# MotoBot.net
KiCad netlist of a schematic drawn in Altium Designer
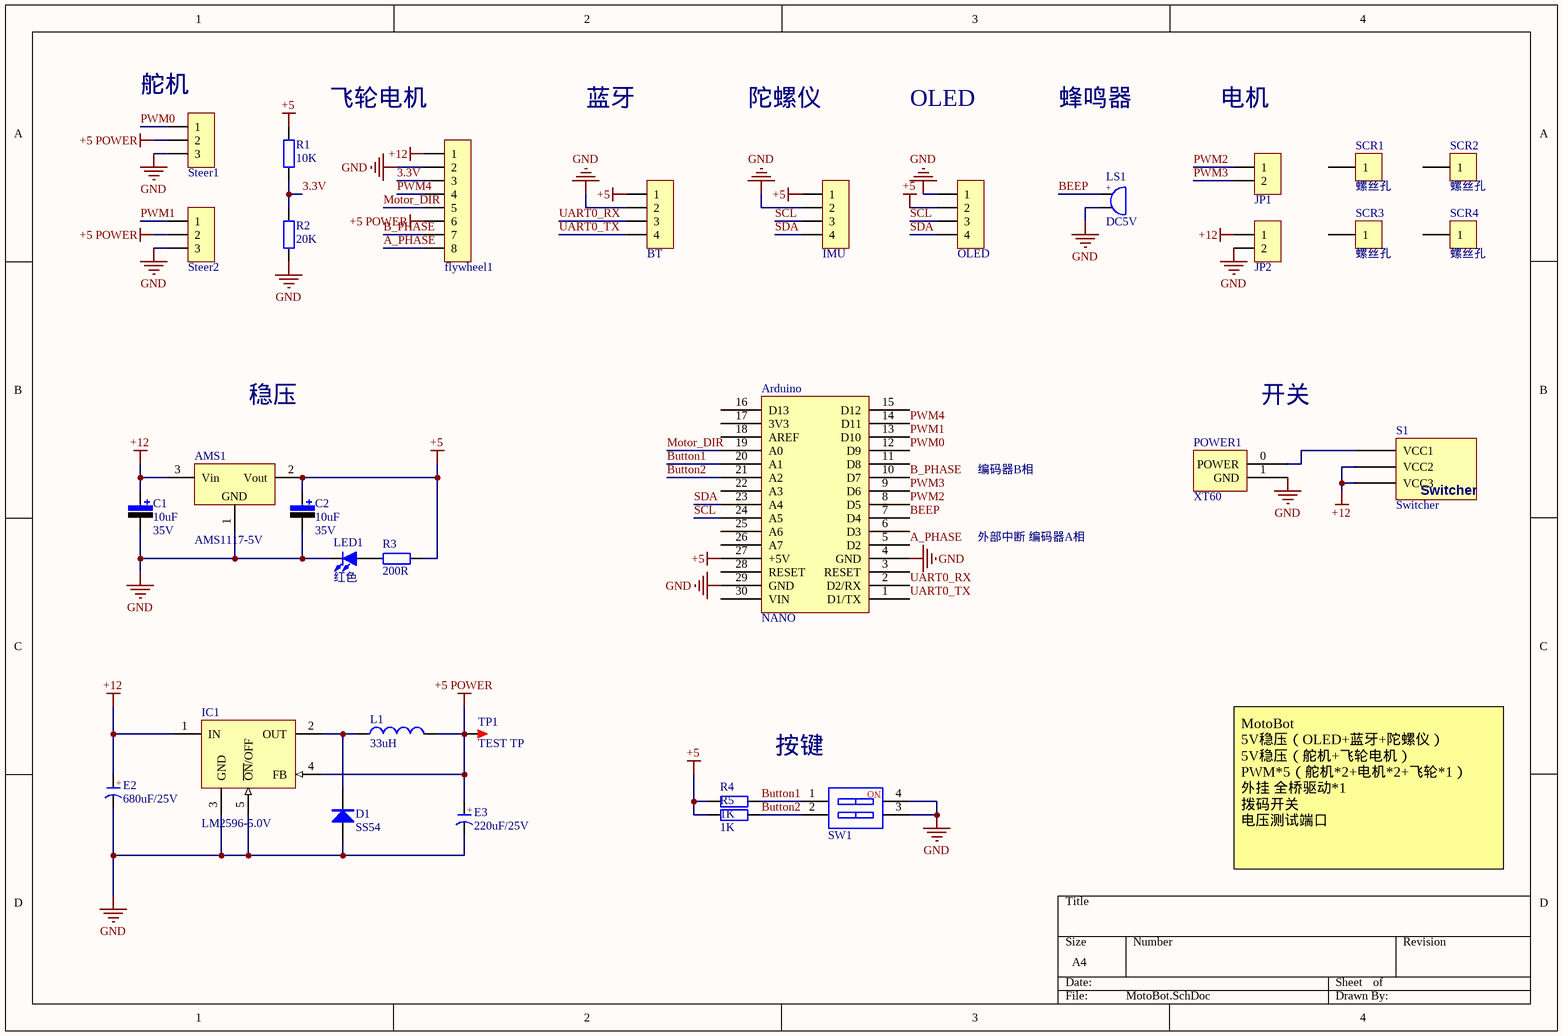
[diagram p0: MotoBot.SchDoc]

(export (version "E")
  (design (tool "Eeschema 10.0.6"))
  (components
    (comp (ref "AMS1")
      (value "AMS1117-5V")
      (footprint "SOT-223")
      (description "三端稳压芯片")
      (fields (field (name "版权归属") "黎明电子style"))
      (libsource (lib "IC芯片") (part "AMS1117"))
    )
    (comp (ref "Arduino") (value "NANO") (footprint "NANO") (libsource (lib "附加模块") (part "NANO")))
    (comp (ref "BT")
      (value "HDR-1X4")
      (footprint "HDR-1X4_M")
      (description "4P接插件")
      (fields (field (name "版权归属") "黎明电子style"))
      (libsource (lib "接插件") (part "Header 4"))
    )
    (comp (ref "C1")
      (value "10uF")
      (footprint "CAP-7343")
      (description "极性电解电容")
      (fields
        (field (name "VOL") "35V")
        (field (name "Comment") "Cap Pol")
        (field (name "PUBLISHER") "Altium Limited")
      )
      (libsource (lib "Fszhang") (part "Cap Pol"))
    )
    (comp (ref "C2")
      (value "10uF")
      (footprint "CAP-7343")
      (description "极性电解电容")
      (fields
        (field (name "VOL") "35V")
        (field (name "Comment") "Cap Pol")
        (field (name "PUBLISHER") "Altium Limited")
      )
      (libsource (lib "Fszhang") (part "Cap Pol"))
    )
    (comp (ref "D1")
      (value "SS54")
      (footprint "SMA")
      (description "肖特基二极管")
      (fields (field (name "版权归属") "源创客"))
      (libsource (lib "8.1   - 二极管-整流桥") (part "SS14"))
    )
    (comp (ref "E2")
      (value "680uF/25V")
      (footprint "CAP 3.5*8*11.5")
      (description "直插电解电容")
      (fields (field (name "版权归属") "源创客"))
      (libsource (lib "3.1   - 电阻-电容-电感") (part "C-CAP"))
    )
    (comp (ref "E3")
      (value "220uF/25V")
      (footprint "CAP 2.0*5*11")
      (description "直插电解电容")
      (fields (field (name "版权归属") "源创客"))
      (libsource (lib "3.1   - 电阻-电容-电感") (part "C-CAP"))
    )
    (comp (ref "flywheel1")
      (value "HDR-1X8")
      (footprint "ZH1.5-WI-8P")
      (description "8P接插件")
      (fields (field (name "版权归属") "源创客"))
      (libsource (lib "4.3   - 接插件-脚距1.5") (part "Header 8"))
    )
    (comp (ref "IC1")
      (value "LM2596-5.0V")
      (footprint "TO263-5A")
      (description "DC降压芯片")
      (fields (field (name "版权归属") "源创客"))
      (libsource (lib "1.3   - 电源类芯片") (part "LM2596-5.0"))
    )
    (comp (ref "IMU")
      (value "HDR-1X4")
      (footprint "HDR-1X4_M")
      (description "4P接插件")
      (fields (field (name "版权归属") "黎明电子style"))
      (libsource (lib "接插件") (part "Header 4"))
    )
    (comp (ref "JP1")
      (value "HDR-1X2")
      (footprint "KF128-5.08-2P")
      (description "2P接插件")
      (fields (field (name "版权归属") "源创客"))
      (libsource (lib "4.10 - 接插件-脚距5.08") (part "Header 2"))
    )
    (comp (ref "JP2")
      (value "HDR-1X2")
      (footprint "KF128-5.08-2P")
      (description "2P接插件")
      (fields (field (name "版权归属") "源创客"))
      (libsource (lib "4.10 - 接插件-脚距5.08") (part "Header 2"))
    )
    (comp (ref "L1") (value "33uH") (footprint "CDRH74") (libsource (lib "K60") (part "Inductor")))
    (comp (ref "LED1")
      (value "红色")
      (footprint "LED 0805W")
      (description "贴片LED")
      (fields (field (name "版权归属") "源创客"))
      (libsource (lib "9.1   - LED") (part "LED-SMD"))
    )
    (comp (ref "LS1")
      (value "DC5V")
      (footprint "BEEP 5x9x5.5")
      (description "蜂鸣器")
      (fields (field (name "版权归属") "源创客"))
      (libsource (lib "15.1 - 未分类器件") (part "BEEP"))
    )
    (comp (ref "OLED")
      (value "HDR-1X4")
      (footprint "HDR-1X4_M")
      (description "4P接插件")
      (fields (field (name "版权归属") "黎明电子style"))
      (libsource (lib "接插件") (part "Header 4"))
    )
    (comp (ref "POWER1")
      (value "XT60")
      (footprint "XT60")
      (libsource (lib "Integrated_Library_CAE") (part "XT60"))
    )
    (comp (ref "R1")
      (value "10K")
      (footprint "R 0805_L")
      (description "贴片电阻")
      (fields (field (name "版权归属") "源创客"))
      (libsource (lib "3.1   - 电阻-电容-电感") (part "R"))
    )
    (comp (ref "R2")
      (value "20K")
      (footprint "R 0805_L")
      (description "贴片电阻")
      (fields (field (name "版权归属") "源创客"))
      (libsource (lib "3.1   - 电阻-电容-电感") (part "R"))
    )
    (comp (ref "R3")
      (value "200R")
      (footprint "R 0805_L")
      (description "贴片电阻")
      (fields (field (name "版权归属") "源创客"))
      (libsource (lib "3.1   - 电阻-电容-电感") (part "R"))
    )
    (comp (ref "R4")
      (value "1K")
      (footprint "R 0805_L")
      (description "贴片电阻")
      (fields (field (name "版权归属") "源创客"))
      (libsource (lib "3.1   - 电阻-电容-电感") (part "R"))
    )
    (comp (ref "R5")
      (value "1K")
      (footprint "R 0805_L")
      (description "贴片电阻")
      (fields (field (name "版权归属") "源创客"))
      (libsource (lib "3.1   - 电阻-电容-电感") (part "R"))
    )
    (comp (ref "S1")
      (value "Switcher")
      (footprint "ThreeSwitcher")
      (libsource (lib "K60") (part "3_Switcher"))
    )
    (comp (ref "SCR1")
      (value "螺丝孔")
      (footprint "LQ_SCROW3&5mm")
      (description "Connector")
      (libsource (lib "LQ-RT1052VCMBVF") (part "CON1"))
    )
    (comp (ref "SCR2")
      (value "螺丝孔")
      (footprint "LQ_SCROW3&5mm")
      (description "Connector")
      (libsource (lib "LQ-RT1052VCMBVF") (part "CON1"))
    )
    (comp (ref "SCR3")
      (value "螺丝孔")
      (footprint "LQ_SCROW3&5mm")
      (description "Connector")
      (libsource (lib "LQ-RT1052VCMBVF") (part "CON1"))
    )
    (comp (ref "SCR4")
      (value "螺丝孔")
      (footprint "LQ_SCROW3&5mm")
      (description "Connector")
      (libsource (lib "LQ-RT1052VCMBVF") (part "CON1"))
    )
    (comp (ref "Steer1")
      (value "HDR-1X3")
      (footprint "HDR-1X3")
      (description "3P接插件")
      (fields (field (name "版权归属") "黎明电子style"))
      (libsource (lib "接插件") (part "Header 3"))
    )
    (comp (ref "Steer2")
      (value "HDR-1X3")
      (footprint "HDR-1X3")
      (description "3P接插件")
      (fields (field (name "版权归属") "黎明电子style"))
      (libsource (lib "接插件") (part "Header 3"))
    )
    (comp (ref "SW1")
      (value "CSW-2P")
      (footprint "CSW DIP-2P")
      (description "2路编码开关")
      (fields (field (name "版权归属") "源创客"))
      (libsource (lib "5.1   - 按键-开关") (part "CSW-2P"))
    )
    (comp (ref "TP1")
      (value "TEST TP")
      (footprint "TEST TP1.4_B")
      (description "测试环")
      (fields (field (name "版权归属") "源创客"))
      (libsource (lib "15.1 - 未分类器件") (part "TEST TP"))
    )
  )
  (nets
    (net (code "1") (name "+5") (class "Default")
      (node (ref "AMS1") (pin "2") (pinfunction "Vout_2") (pintype "passive"))
      (node (ref "Arduino") (pin "27") (pinfunction "+5V_27") (pintype "passive"))
      (node (ref "BT") (pin "1") (pinfunction "1_1") (pintype "passive"))
      (node (ref "C2") (pin "1") (pinfunction "1_1") (pintype "passive"))
      (node (ref "IMU") (pin "1") (pinfunction "1_1") (pintype "passive"))
      (node (ref "OLED") (pin "2") (pinfunction "2_2") (pintype "passive"))
      (node (ref "R1") (pin "1") (pinfunction "1_1") (pintype "passive"))
      (node (ref "R3") (pin "2") (pinfunction "2_2") (pintype "passive"))
      (node (ref "R4") (pin "1") (pinfunction "1_1") (pintype "passive"))
      (node (ref "R5") (pin "1") (pinfunction "1_1") (pintype "passive"))
    )
    (net (code "2") (name "+5 POWER") (class "Default")
      (node (ref "E3") (pin "1") (pinfunction "A_1") (pintype "passive"))
      (node (ref "IC1") (pin "4") (pinfunction "FB_4") (pintype "input"))
      (node (ref "L1") (pin "2") (pinfunction "2_2") (pintype "passive"))
      (node (ref "Steer1") (pin "2") (pinfunction "2_2") (pintype "passive"))
      (node (ref "Steer2") (pin "2") (pinfunction "2_2") (pintype "passive"))
      (node (ref "TP1") (pin "1") (pinfunction "1_1") (pintype "passive"))
      (node (ref "flywheel1") (pin "6") (pinfunction "6_6") (pintype "passive"))
    )
    (net (code "3") (name "+12") (class "Default")
      (node (ref "AMS1") (pin "3") (pinfunction "Vin_3") (pintype "passive"))
      (node (ref "C1") (pin "1") (pinfunction "1_1") (pintype "passive"))
      (node (ref "E2") (pin "1") (pinfunction "A_1") (pintype "passive"))
      (node (ref "IC1") (pin "1") (pinfunction "IN_1") (pintype "power_in"))
      (node (ref "JP2") (pin "1") (pinfunction "1_1") (pintype "passive"))
      (node (ref "S1") (pin "VCC2") (pinfunction "VCC2_VCC2") (pintype "power_in"))
      (node (ref "S1") (pin "VCC3") (pinfunction "VCC3_VCC3") (pintype "power_in"))
      (node (ref "flywheel1") (pin "1") (pinfunction "1_1") (pintype "passive"))
    )
    (net (code "4") (name "/3.3V") (class "Default")
      (node (ref "R1") (pin "2") (pinfunction "2_2") (pintype "passive"))
      (node (ref "R2") (pin "1") (pinfunction "1_1") (pintype "passive"))
      (node (ref "flywheel1") (pin "3") (pinfunction "3_3") (pintype "passive"))
    )
    (net (code "6") (name "/A_PHASE") (class "Default")
      (node (ref "Arduino") (pin "5") (pinfunction "D2_5") (pintype "passive"))
      (node (ref "flywheel1") (pin "8") (pinfunction "8_8") (pintype "passive"))
    )
    (net (code "7") (name "/BEEP") (class "Default")
      (node (ref "Arduino") (pin "7") (pinfunction "D4_7") (pintype "passive"))
      (node (ref "LS1") (pin "1") (pinfunction "1_1") (pintype "passive"))
    )
    (net (code "8") (name "/B_PHASE") (class "Default")
      (node (ref "Arduino") (pin "10") (pinfunction "D7_10") (pintype "passive"))
      (node (ref "flywheel1") (pin "7") (pinfunction "7_7") (pintype "passive"))
    )
    (net (code "9") (name "/Button1") (class "Default")
      (node (ref "Arduino") (pin "20") (pinfunction "A1_20") (pintype "passive"))
      (node (ref "R4") (pin "2") (pinfunction "2_2") (pintype "passive"))
      (node (ref "SW1") (pin "1") (pinfunction "1_1") (pintype "passive"))
    )
    (net (code "10") (name "/Button2") (class "Default")
      (node (ref "Arduino") (pin "21") (pinfunction "A2_21") (pintype "passive"))
      (node (ref "R5") (pin "2") (pinfunction "2_2") (pintype "passive"))
      (node (ref "SW1") (pin "2") (pinfunction "2_2") (pintype "passive"))
    )
    (net (code "11") (name "/Motor_DIR") (class "Default")
      (node (ref "Arduino") (pin "19") (pinfunction "A0_19") (pintype "passive"))
      (node (ref "flywheel1") (pin "5") (pinfunction "5_5") (pintype "passive"))
    )
    (net (code "12") (name "/PWM0") (class "Default")
      (node (ref "Arduino") (pin "12") (pinfunction "D9_12") (pintype "passive"))
      (node (ref "Steer1") (pin "1") (pinfunction "1_1") (pintype "passive"))
    )
    (net (code "13") (name "/PWM1") (class "Default")
      (node (ref "Arduino") (pin "13") (pinfunction "D10_13") (pintype "passive"))
      (node (ref "Steer2") (pin "1") (pinfunction "1_1") (pintype "passive"))
    )
    (net (code "14") (name "/PWM2") (class "Default")
      (node (ref "Arduino") (pin "8") (pinfunction "D5_8") (pintype "passive"))
      (node (ref "JP1") (pin "1") (pinfunction "1_1") (pintype "passive"))
    )
    (net (code "15") (name "/PWM3") (class "Default")
      (node (ref "Arduino") (pin "9") (pinfunction "D6_9") (pintype "passive"))
      (node (ref "JP1") (pin "2") (pinfunction "2_2") (pintype "passive"))
    )
    (net (code "16") (name "/PWM4") (class "Default")
      (node (ref "Arduino") (pin "14") (pinfunction "D11_14") (pintype "passive"))
      (node (ref "flywheel1") (pin "4") (pinfunction "4_4") (pintype "passive"))
    )
    (net (code "17") (name "/SCL") (class "Default")
      (node (ref "Arduino") (pin "24") (pinfunction "A5_24") (pintype "passive"))
      (node (ref "IMU") (pin "3") (pinfunction "3_3") (pintype "passive"))
      (node (ref "OLED") (pin "3") (pinfunction "3_3") (pintype "passive"))
    )
    (net (code "18") (name "/SDA") (class "Default")
      (node (ref "Arduino") (pin "23") (pinfunction "A4_23") (pintype "passive"))
      (node (ref "IMU") (pin "4") (pinfunction "4_4") (pintype "passive"))
      (node (ref "OLED") (pin "4") (pinfunction "4_4") (pintype "passive"))
    )
    (net (code "19") (name "/UART0_RX") (class "Default")
      (node (ref "Arduino") (pin "2") (pinfunction "D2/RX_2") (pintype "passive"))
      (node (ref "BT") (pin "3") (pinfunction "3_3") (pintype "passive"))
    )
    (net (code "20") (name "/UART0_TX") (class "Default")
      (node (ref "Arduino") (pin "1") (pinfunction "D1/TX_1") (pintype "passive"))
      (node (ref "BT") (pin "4") (pinfunction "4_4") (pintype "passive"))
    )
    (net (code "21") (name "GND") (class "Default")
      (node (ref "AMS1") (pin "1") (pinfunction "GND_1") (pintype "passive"))
      (node (ref "Arduino") (pin "29") (pinfunction "GND_29") (pintype "passive"))
      (node (ref "Arduino") (pin "4") (pinfunction "GND_4") (pintype "passive"))
      (node (ref "BT") (pin "2") (pinfunction "2_2") (pintype "passive"))
      (node (ref "C1") (pin "2") (pinfunction "2_2") (pintype "passive"))
      (node (ref "C2") (pin "2") (pinfunction "2_2") (pintype "passive"))
      (node (ref "D1") (pin "1") (pinfunction "A_1") (pintype "passive"))
      (node (ref "E2") (pin "2") (pinfunction "K_2") (pintype "passive"))
      (node (ref "E3") (pin "2") (pinfunction "K_2") (pintype "passive"))
      (node (ref "IC1") (pin "3") (pinfunction "GND_3") (pintype "power_in"))
      (node (ref "IC1") (pin "5") (pinfunction "~{ON}/OFF_5") (pintype "input"))
      (node (ref "IMU") (pin "2") (pinfunction "2_2") (pintype "passive"))
      (node (ref "JP2") (pin "2") (pinfunction "2_2") (pintype "passive"))
      (node (ref "LED1") (pin "2") (pinfunction "K_2") (pintype "passive"))
      (node (ref "LS1") (pin "2") (pinfunction "2_2") (pintype "passive"))
      (node (ref "OLED") (pin "1") (pinfunction "1_1") (pintype "passive"))
      (node (ref "POWER1") (pin "1") (pinfunction "GND_1") (pintype "passive"))
      (node (ref "R2") (pin "2") (pinfunction "2_2") (pintype "passive"))
      (node (ref "SW1") (pin "3") (pinfunction "3_3") (pintype "passive"))
      (node (ref "SW1") (pin "4") (pinfunction "4_4") (pintype "passive"))
      (node (ref "Steer1") (pin "3") (pinfunction "3_3") (pintype "passive"))
      (node (ref "Steer2") (pin "3") (pinfunction "3_3") (pintype "passive"))
      (node (ref "flywheel1") (pin "2") (pinfunction "2_2") (pintype "passive"))
    )
    (net (code "22") (name "Net-(D1-K)") (class "Default")
      (node (ref "D1") (pin "2") (pinfunction "K_2") (pintype "passive"))
      (node (ref "IC1") (pin "2") (pinfunction "OUT_2") (pintype "power_in"))
      (node (ref "L1") (pin "1") (pinfunction "1_1") (pintype "passive"))
    )
    (net (code "23") (name "Net-(LED1-A)") (class "Default")
      (node (ref "LED1") (pin "1") (pinfunction "A_1") (pintype "passive"))
      (node (ref "R3") (pin "1") (pinfunction "1_1") (pintype "passive"))
    )
    (net (code "24") (name "Net-(POWER1-POWER)") (class "Default")
      (node (ref "POWER1") (pin "0") (pinfunction "POWER_0") (pintype "passive"))
      (node (ref "S1") (pin "VCC1") (pinfunction "VCC1_VCC1") (pintype "power_in"))
    )
    (net (code "25") (name "unconnected-(Arduino-3V3-Pad17)") (class "Default")
      (node (ref "Arduino") (pin "17") (pinfunction "3V3_17") (pintype "passive"))
    )
    (net (code "26") (name "unconnected-(Arduino-A3-Pad22)") (class "Default")
      (node (ref "Arduino") (pin "22") (pinfunction "A3_22") (pintype "passive"))
    )
    (net (code "27") (name "unconnected-(Arduino-A6-Pad25)") (class "Default")
      (node (ref "Arduino") (pin "25") (pinfunction "A6_25") (pintype "passive"))
    )
    (net (code "28") (name "unconnected-(Arduino-A7-Pad26)") (class "Default")
      (node (ref "Arduino") (pin "26") (pinfunction "A7_26") (pintype "passive"))
    )
    (net (code "29") (name "unconnected-(Arduino-AREF-Pad18)") (class "Default")
      (node (ref "Arduino") (pin "18") (pinfunction "AREF_18") (pintype "passive"))
    )
    (net (code "30") (name "unconnected-(Arduino-D3-Pad6)") (class "Default")
      (node (ref "Arduino") (pin "6") (pinfunction "D3_6") (pintype "passive"))
    )
    (net (code "31") (name "unconnected-(Arduino-D8-Pad11)") (class "Default")
      (node (ref "Arduino") (pin "11") (pinfunction "D8_11") (pintype "passive"))
    )
    (net (code "32") (name "unconnected-(Arduino-D12-Pad15)") (class "Default")
      (node (ref "Arduino") (pin "15") (pinfunction "D12_15") (pintype "passive"))
    )
    (net (code "33") (name "unconnected-(Arduino-D13-Pad16)") (class "Default")
      (node (ref "Arduino") (pin "16") (pinfunction "D13_16") (pintype "passive"))
    )
    (net (code "34") (name "unconnected-(Arduino-RESET-Pad3)") (class "Default")
      (node (ref "Arduino") (pin "3") (pinfunction "RESET_3") (pintype "passive"))
    )
    (net (code "35") (name "unconnected-(Arduino-RESET-Pad28)") (class "Default")
      (node (ref "Arduino") (pin "28") (pinfunction "RESET_28") (pintype "passive"))
    )
    (net (code "36") (name "unconnected-(Arduino-VIN-Pad30)") (class "Default")
      (node (ref "Arduino") (pin "30") (pinfunction "VIN_30") (pintype "passive"))
    )
    (net (code "37") (name "unconnected-(SCR1-Pad1)") (class "Default")
      (node (ref "SCR1") (pin "1") (pinfunction "1_1") (pintype "passive"))
    )
    (net (code "38") (name "unconnected-(SCR2-Pad1)") (class "Default")
      (node (ref "SCR2") (pin "1") (pinfunction "1_1") (pintype "passive"))
    )
    (net (code "39") (name "unconnected-(SCR3-Pad1)") (class "Default")
      (node (ref "SCR3") (pin "1") (pinfunction "1_1") (pintype "passive"))
    )
    (net (code "40") (name "unconnected-(SCR4-Pad1)") (class "Default")
      (node (ref "SCR4") (pin "1") (pinfunction "1_1") (pintype "passive"))
    )
  )
)
